# tritiled_v30_batt_pcb.net
KiCad netlist of a schematic drawn in EAGLE
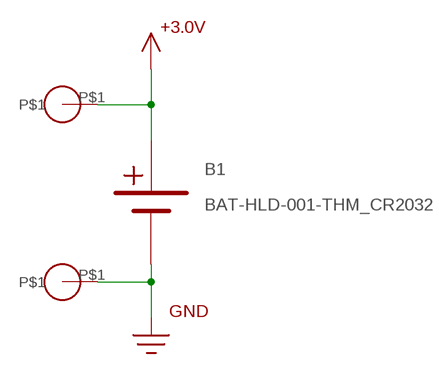
[diagram p0: schematic, sheet 1]

(export (version "E")
  (design (tool "Eeschema 10.0.6"))
  (components
    (comp (ref "B1")
      (value "BAT-HLD-001-THM_CR2032")
      (footprint "eagle-import:CR2032_BAT-HLD-001-THM")
      (libsource (lib "eagle-import") (part "BAT-HLD-001-THM_CR2032"))
    )
    (comp (ref "U$1")
      (value "HDR_1_PIN")
      (footprint "eagle-import:HDR_1_PIN")
      (libsource (lib "eagle-import") (part "HDR_1_PIN"))
    )
    (comp (ref "U$2")
      (value "HDR_1_PIN")
      (footprint "eagle-import:HDR_1_PIN")
      (libsource (lib "eagle-import") (part "HDR_1_PIN"))
    )
  )
  (nets
    (net (code "1") (name "+3.0V") (class "Default")
      (node (ref "B1") (pin "+V@1") (pinfunction "+V_+V@1") (pintype "power_in"))
      (node (ref "B1") (pin "+V@2") (pinfunction "+V_+V@2") (pintype "power_in"))
      (node (ref "B1") (pin "+V@3") (pinfunction "+V_+V@3") (pintype "power_in"))
      (node (ref "B1") (pin "+V@4") (pinfunction "+V_+V@4") (pintype "power_in"))
      (node (ref "U$1") (pin "P$1") (pinfunction "P$1_P$1") (pintype "bidirectional"))
    )
    (net (code "2") (name "GND") (class "Default")
      (node (ref "B1") (pin "GND") (pinfunction "0V_GND") (pintype "power_in"))
      (node (ref "U$2") (pin "P$1") (pinfunction "P$1_P$1") (pintype "bidirectional"))
    )
  )
)
